# UV_LED.net
KiCad netlist of a schematic drawn in Altium Designer
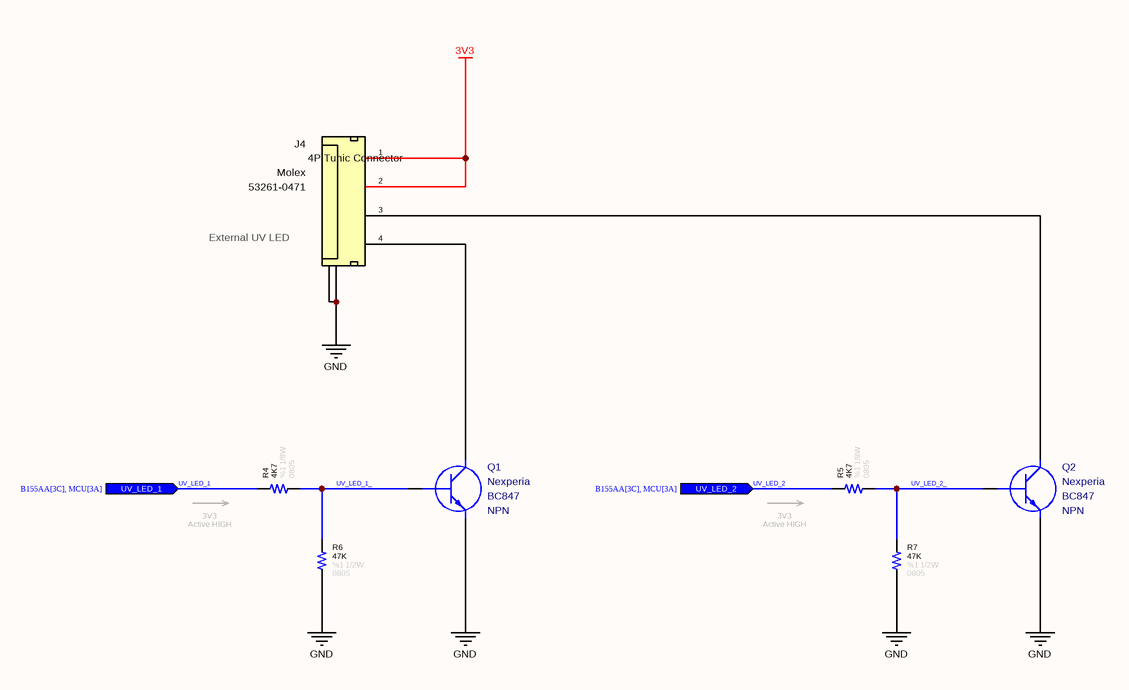
[diagram p0: UV LED.SchDoc]

(export (version "E")
  (design (tool "Eeschema 10.0.6"))
  (components
    (comp (ref "J4")
      (value "4P SMD Tunic Connector")
      (footprint "Connector_Tunic 4P")
      (description "Mini Tunic Connector with 4P")
      (fields
        (field (name "MANUFACTURER NAME") "Molex")
        (field (name "MANUFACTURER PART NUMBER") "53261-0471")
      )
      (libsource (lib "Akkoyun") (part "Connector - Mini Tunic 4P (1.25)"))
    )
    (comp (ref "Q1")
      (value "BC847AQAZ")
      (footprint "SOT-23-3")
      (description "Bipolar NPN Transistors")
      (fields
        (field (name "MANUFACTURER NAME") "Nexperia")
        (field (name "MANUFACTURER PART NUMBER") "BC847")
        (field (name "POLARITY") "NPN")
      )
      (libsource (lib "Akkoyun") (part "Transistor - BC847 (SOT23-3)"))
    )
    (comp (ref "Q2")
      (value "BC847AQAZ")
      (footprint "SOT-23-3")
      (description "Bipolar NPN Transistors")
      (fields
        (field (name "MANUFACTURER NAME") "Nexperia")
        (field (name "MANUFACTURER PART NUMBER") "BC847")
        (field (name "POLARITY") "NPN")
      )
      (libsource (lib "Akkoyun") (part "Transistor - BC847 (SOT23-3)"))
    )
    (comp (ref "R4")
      (value "4K7")
      (footprint "RESISTOR_0805")
      (description "Thick Film Resistors - SMD 1/16 W 4.7 KOhm 1%")
      (fields
        (field (name "MANUFACTURER PART NUMBER") "CRCW08054K70FKEC")
        (field (name "TOLERANCE") "%1")
        (field (name "CASE") "0805")
        (field (name "POWER") "1/8W")
        (field (name "Comment") "4K7 - 0805 - %1 - 1/16W")
      )
      (libsource (lib "Akkoyun") (part "Resistor - 4K7 [0805]"))
    )
    (comp (ref "R5")
      (value "4K7")
      (footprint "RESISTOR_0805")
      (description "Thick Film Resistors - SMD 1/16 W 4.7 KOhm 1%")
      (fields
        (field (name "MANUFACTURER PART NUMBER") "CRCW08054K70FKEC")
        (field (name "TOLERANCE") "%1")
        (field (name "CASE") "0805")
        (field (name "POWER") "1/8W")
        (field (name "Comment") "4K7 - 0805 - %1 - 1/16W")
      )
      (libsource (lib "Akkoyun") (part "Resistor - 4K7 [0805]"))
    )
    (comp (ref "R6")
      (value "47K")
      (footprint "RESISTOR_0805")
      (description "Thick Film Resistors - SMD 1/2 W 47 KOhm 1%")
      (fields
        (field (name "MANUFACTURER PART NUMBER") "CRCW080547K0FKECHP")
        (field (name "TOLERANCE") "%1")
        (field (name "CASE") "0805")
        (field (name "POWER") "1/2W")
        (field (name "Comment") "47K - 0805 - %1 - 1/2W")
      )
      (libsource (lib "Akkoyun") (part "Resistor - 47K [0805]"))
    )
    (comp (ref "R7")
      (value "47K")
      (footprint "RESISTOR_0805")
      (description "Thick Film Resistors - SMD 1/2 W 47 KOhm 1%")
      (fields
        (field (name "MANUFACTURER PART NUMBER") "CRCW080547K0FKECHP")
        (field (name "TOLERANCE") "%1")
        (field (name "CASE") "0805")
        (field (name "POWER") "1/2W")
        (field (name "Comment") "47K - 0805 - %1 - 1/2W")
      )
      (libsource (lib "Akkoyun") (part "Resistor - 47K [0805]"))
    )
  )
  (nets
    (net (code "1") (name "/UV_LED_1") (class "Default")
      (node (ref "R4") (pin "2") (pinfunction "2_2") (pintype "passive"))
    )
    (net (code "2") (name "/UV_LED_1_") (class "Default")
      (node (ref "Q1") (pin "1") (pinfunction "B_1") (pintype "passive"))
      (node (ref "R4") (pin "1") (pinfunction "1_1") (pintype "passive"))
      (node (ref "R6") (pin "2") (pinfunction "2_2") (pintype "passive"))
    )
    (net (code "3") (name "/UV_LED_2") (class "Default")
      (node (ref "R5") (pin "2") (pinfunction "2_2") (pintype "passive"))
    )
    (net (code "4") (name "/UV_LED_2_") (class "Default")
      (node (ref "Q2") (pin "1") (pinfunction "B_1") (pintype "passive"))
      (node (ref "R5") (pin "1") (pinfunction "1_1") (pintype "passive"))
      (node (ref "R7") (pin "2") (pinfunction "2_2") (pintype "passive"))
    )
    (net (code "5") (name "3V3") (class "Default")
      (node (ref "J4") (pin "1") (pinfunction "BAT+_1") (pintype "passive"))
      (node (ref "J4") (pin "2") (pinfunction "BAT+_2") (pintype "passive"))
    )
    (net (code "6") (name "GND") (class "Default")
      (node (ref "J4") (pin "5") (pinfunction "GND_5") (pintype "passive"))
      (node (ref "J4") (pin "6") (pinfunction "GND_6") (pintype "passive"))
      (node (ref "Q1") (pin "2") (pinfunction "E_2") (pintype "passive"))
      (node (ref "Q2") (pin "2") (pinfunction "E_2") (pintype "passive"))
      (node (ref "R6") (pin "1") (pinfunction "1_1") (pintype "passive"))
      (node (ref "R7") (pin "1") (pinfunction "1_1") (pintype "passive"))
    )
    (net (code "7") (name "Net-(Q1-C)") (class "Default")
      (node (ref "J4") (pin "4") (pinfunction "BAT-_4") (pintype "passive"))
      (node (ref "Q1") (pin "3") (pinfunction "C_3") (pintype "passive"))
    )
    (net (code "8") (name "Net-(Q2-C)") (class "Default")
      (node (ref "J4") (pin "3") (pinfunction "BAT-_3") (pintype "passive"))
      (node (ref "Q2") (pin "3") (pinfunction "C_3") (pintype "passive"))
    )
  )
)
